# EDU_High-Speed-Design_CPU_Control.net
KiCad netlist of a schematic drawn in Altium Designer
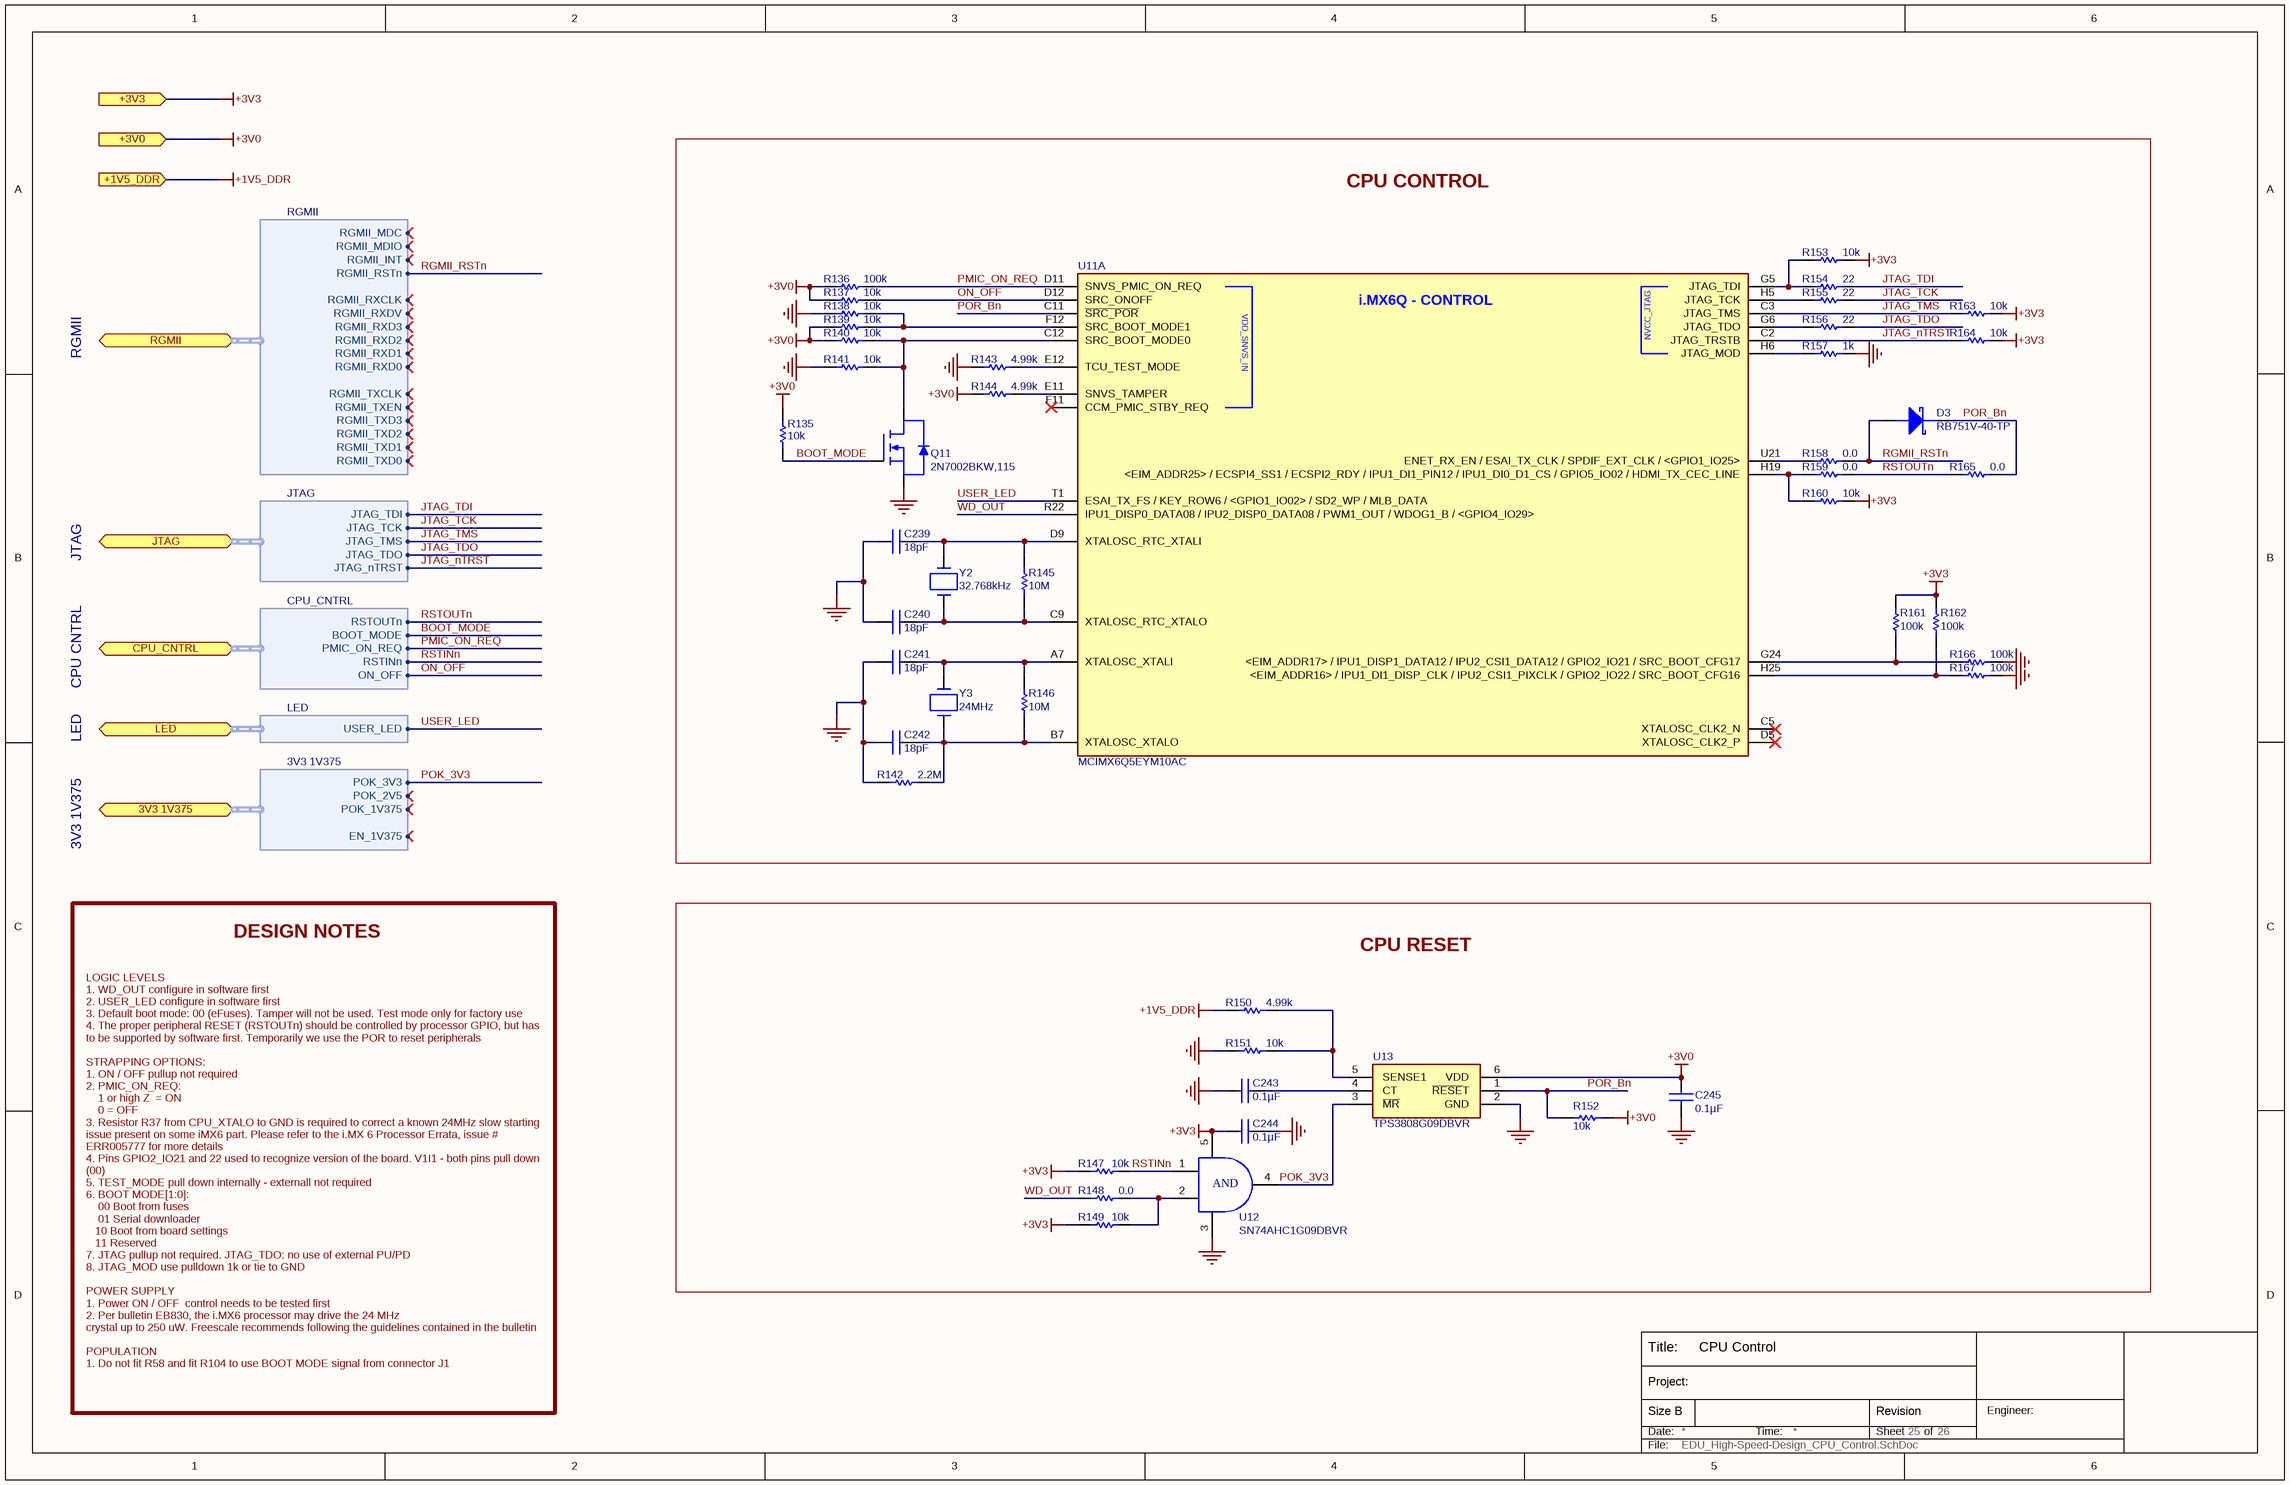
[diagram p0: EDU_High-Speed-Design_CPU_Control.SchDoc]

(export (version "E")
  (design (tool "Eeschema 10.0.6"))
  (components
    (comp (ref "C239")
      (value "18pF")
      (footprint "C0402")
      (description "CAP CER 18PF 50V C0G 5% 0402")
      (fields (field (name "VOLTAGE") "50V"))
      (libsource (lib "EDU_High-Speed-Design") (part "C1005C0G1H180J"))
    )
    (comp (ref "C240")
      (value "18pF")
      (footprint "C0402")
      (description "CAP CER 18PF 50V C0G 5% 0402")
      (fields (field (name "VOLTAGE") "50V"))
      (libsource (lib "EDU_High-Speed-Design") (part "C1005C0G1H180J"))
    )
    (comp (ref "C241")
      (value "18pF")
      (footprint "C0402")
      (description "CAP CER 18PF 50V C0G 5% 0402")
      (fields (field (name "VOLTAGE") "50V"))
      (libsource (lib "EDU_High-Speed-Design") (part "C1005C0G1H180J"))
    )
    (comp (ref "C242")
      (value "18pF")
      (footprint "C0402")
      (description "CAP CER 18PF 50V C0G 5% 0402")
      (fields (field (name "VOLTAGE") "50V"))
      (libsource (lib "EDU_High-Speed-Design") (part "C1005C0G1H180J"))
    )
    (comp (ref "C243")
      (value "0.1µF")
      (footprint "C0402")
      (description "CAP CER .10UF 50V X5R 10% 0402")
      (fields (field (name "VOLTAGE") "50V"))
      (libsource (lib "EDU_High-Speed-Design") (part "C1005X5R1H104K"))
    )
    (comp (ref "C244")
      (value "0.1µF")
      (footprint "C0402")
      (description "CAP CER .10UF 50V X5R 10% 0402")
      (fields (field (name "VOLTAGE") "50V"))
      (libsource (lib "EDU_High-Speed-Design") (part "C1005X5R1H104K"))
    )
    (comp (ref "C245")
      (value "0.1µF")
      (footprint "C0402")
      (description "CAP CER .10UF 50V X5R 10% 0402")
      (fields (field (name "VOLTAGE") "50V"))
      (libsource (lib "EDU_High-Speed-Design") (part "C1005X5R1H104K"))
    )
    (comp (ref "D3")
      (value "RB751V-40-TP")
      (footprint "SOD-323")
      (description "DIODE SCHTKY 30MA 30V SOD-323")
      (libsource (lib "EDU_High-Speed-Design") (part "RB751V-40-TP"))
    )
    (comp (ref "Q11")
      (value "2N7002BKW,115")
      (footprint "SOT-23-3")
      (description "MOSFET N-CH 60V 310MA SOT323")
      (libsource (lib "EDU_High-Speed-Design") (part "2N7002BKW,115"))
    )
    (comp (ref "R135")
      (value "10k")
      (footprint "R0402")
      (description "RES 10.0K OHM 1/16W 1% 0402 SMD")
      (libsource (lib "EDU_High-Speed-Design") (part "RC0402FR-0710KL"))
    )
    (comp (ref "R136")
      (value "100k")
      (footprint "R0402")
      (description "RES 100K OHM 1/16W 1% 0402 SMD")
      (libsource (lib "EDU_High-Speed-Design") (part "RMCF0402FT100K"))
    )
    (comp (ref "R137")
      (value "10k")
      (footprint "R0402")
      (description "RES 10.0K OHM 1/16W 1% 0402 SMD")
      (libsource (lib "EDU_High-Speed-Design") (part "RC0402FR-0710KL"))
    )
    (comp (ref "R138")
      (value "10k")
      (footprint "R0402")
      (description "RES 10.0K OHM 1/16W 1% 0402 SMD")
      (libsource (lib "EDU_High-Speed-Design") (part "RC0402FR-0710KL"))
    )
    (comp (ref "R139")
      (value "10k")
      (footprint "R0402")
      (description "RES 10.0K OHM 1/16W 1% 0402 SMD")
      (libsource (lib "EDU_High-Speed-Design") (part "RC0402FR-0710KL"))
    )
    (comp (ref "R140")
      (value "10k")
      (footprint "R0402")
      (description "RES 10.0K OHM 1/16W 1% 0402 SMD")
      (libsource (lib "EDU_High-Speed-Design") (part "RC0402FR-0710KL"))
    )
    (comp (ref "R141")
      (value "10k")
      (footprint "R0402")
      (description "RES 10.0K OHM 1/16W 1% 0402 SMD")
      (libsource (lib "EDU_High-Speed-Design") (part "RC0402FR-0710KL"))
    )
    (comp (ref "R142")
      (value "2.2M")
      (footprint "R0402")
      (description "RES 2.20M OHM 1/16W 1% 0402 SMD")
      (libsource (lib "EDU_High-Speed-Design") (part "CRCW04022M20FKED"))
    )
    (comp (ref "R143")
      (value "4.99k")
      (footprint "R0402")
      (description "RES TF 4.99K OHM 1% 1/16W 0402")
      (libsource (lib "EDU_High-Speed-Design") (part "RMCF0402FT4K99"))
    )
    (comp (ref "R144")
      (value "4.99k")
      (footprint "R0402")
      (description "RES TF 4.99K OHM 1% 1/16W 0402")
      (libsource (lib "EDU_High-Speed-Design") (part "RMCF0402FT4K99"))
    )
    (comp (ref "R145")
      (value "10M")
      (footprint "R0402")
      (description "RES 10.0M OHM 1/16W 1% 0402 SMD")
      (libsource (lib "EDU_High-Speed-Design") (part "CRCW040210M0FKED"))
    )
    (comp (ref "R146")
      (value "10M")
      (footprint "R0402")
      (description "RES 10.0M OHM 1/16W 1% 0402 SMD")
      (libsource (lib "EDU_High-Speed-Design") (part "CRCW040210M0FKED"))
    )
    (comp (ref "R147")
      (value "10k")
      (footprint "R0402")
      (description "RES 10.0K OHM 1/16W 1% 0402 SMD")
      (libsource (lib "EDU_High-Speed-Design") (part "RC0402FR-0710KL"))
    )
    (comp (ref "R148")
      (value "0.0")
      (footprint "R0402")
      (description "RES 0.0 OHM 1/16W 0402 SMD")
      (libsource (lib "EDU_High-Speed-Design") (part "RC0402JR-070RL"))
    )
    (comp (ref "R149")
      (value "10k")
      (footprint "R0402")
      (description "RES 10.0K OHM 1/16W 1% 0402 SMD")
      (libsource (lib "EDU_High-Speed-Design") (part "RC0402FR-0710KL"))
    )
    (comp (ref "R150")
      (value "4.99k")
      (footprint "R0402")
      (description "RES TF 4.99K OHM 1% 1/16W 0402")
      (libsource (lib "EDU_High-Speed-Design") (part "RMCF0402FT4K99"))
    )
    (comp (ref "R151")
      (value "10k")
      (footprint "R0402")
      (description "RES 10.0K OHM 1/16W 1% 0402 SMD")
      (libsource (lib "EDU_High-Speed-Design") (part "RC0402FR-0710KL"))
    )
    (comp (ref "R152")
      (value "10k")
      (footprint "R0402")
      (description "RES 10.0K OHM 1/16W 1% 0402 SMD")
      (libsource (lib "EDU_High-Speed-Design") (part "RC0402FR-0710KL"))
    )
    (comp (ref "R153")
      (value "10k")
      (footprint "R0402")
      (description "RES 10.0K OHM 1/16W 1% 0402 SMD")
      (libsource (lib "EDU_High-Speed-Design") (part "RC0402FR-0710KL"))
    )
    (comp (ref "R154")
      (value "22")
      (footprint "R0402")
      (description "RES 22.0 OHM 1/16W 1% 0402 SMD")
      (libsource (lib "EDU_High-Speed-Design") (part "RC0402FR-0722RL"))
    )
    (comp (ref "R155")
      (value "22")
      (footprint "R0402")
      (description "RES 22.0 OHM 1/16W 1% 0402 SMD")
      (libsource (lib "EDU_High-Speed-Design") (part "RC0402FR-0722RL"))
    )
    (comp (ref "R156")
      (value "22")
      (footprint "R0402")
      (description "RES 22.0 OHM 1/16W 1% 0402 SMD")
      (libsource (lib "EDU_High-Speed-Design") (part "RC0402FR-0722RL"))
    )
    (comp (ref "R157")
      (value "1k")
      (footprint "R0402")
      (description "RES 1.00K OHM 1/16W 1% 0402 SMD")
      (libsource (lib "EDU_High-Speed-Design") (part "RC0402FR-071KL"))
    )
    (comp (ref "R158")
      (value "0.0")
      (footprint "R0402")
      (description "RES 0.0 OHM 1/16W 0402 SMD")
      (libsource (lib "EDU_High-Speed-Design") (part "RC0402JR-070RL"))
    )
    (comp (ref "R159")
      (value "0.0")
      (footprint "R0402")
      (description "RES 0.0 OHM 1/16W 0402 SMD")
      (libsource (lib "EDU_High-Speed-Design") (part "RC0402JR-070RL"))
    )
    (comp (ref "R160")
      (value "10k")
      (footprint "R0402")
      (description "RES 10.0K OHM 1/16W 1% 0402 SMD")
      (libsource (lib "EDU_High-Speed-Design") (part "RC0402FR-0710KL"))
    )
    (comp (ref "R161")
      (value "100k")
      (footprint "R0402")
      (description "RES 100K OHM 1/16W 1% 0402 SMD")
      (libsource (lib "EDU_High-Speed-Design") (part "RMCF0402FT100K"))
    )
    (comp (ref "R162")
      (value "100k")
      (footprint "R0402")
      (description "RES 100K OHM 1/16W 1% 0402 SMD")
      (libsource (lib "EDU_High-Speed-Design") (part "RMCF0402FT100K"))
    )
    (comp (ref "R163")
      (value "10k")
      (footprint "R0402")
      (description "RES 10.0K OHM 1/16W 1% 0402 SMD")
      (libsource (lib "EDU_High-Speed-Design") (part "RC0402FR-0710KL"))
    )
    (comp (ref "R164")
      (value "10k")
      (footprint "R0402")
      (description "RES 10.0K OHM 1/16W 1% 0402 SMD")
      (libsource (lib "EDU_High-Speed-Design") (part "RC0402FR-0710KL"))
    )
    (comp (ref "R165")
      (value "0.0")
      (footprint "R0402")
      (description "RES 0.0 OHM 1/16W 0402 SMD")
      (libsource (lib "EDU_High-Speed-Design") (part "RC0402JR-070RL"))
    )
    (comp (ref "R166")
      (value "100k")
      (footprint "R0402")
      (description "RES 100K OHM 1/16W 1% 0402 SMD")
      (libsource (lib "EDU_High-Speed-Design") (part "RMCF0402FT100K"))
    )
    (comp (ref "R167")
      (value "100k")
      (footprint "R0402")
      (description "RES 100K OHM 1/16W 1% 0402 SMD")
      (libsource (lib "EDU_High-Speed-Design") (part "RMCF0402FT100K"))
    )
    (comp (ref "U11")
      (value "MCIMX6Q5EYM10AC")
      (footprint "MCIMX6Q5EYM10AC")
      (description "IC MCU 32BIT ARM QUAD 624FCBGA")
      (libsource (lib "EDU_High-Speed-Design") (part "MCIMX6Q5EYM10AC"))
    )
    (comp (ref "U12")
      (value "SN74AHC1G09DBVR")
      (footprint "SOT-23-5")
      (description "IC GATE AND SGL 2INP SOT23-5")
      (fields
        (field (name "MANUFACTURER") "Texas Instruments")
        (field (name ".CREATOR") "MM")
        (field (name ".CHECKED PCB") "RF, used by MM")
        (field (name ".CHECKED SCH") "MM, checked by RF")
      )
      (libsource (lib "EDU_High-Speed-Design") (part "SN74AHC1G09DBVR"))
    )
    (comp (ref "U13")
      (value "TPS3808G09DBVR")
      (footprint "SOT-23-6")
      (description "IC VOLT SUPERVISOR 0.9V SOT23-6")
      (libsource (lib "EDU_High-Speed-Design") (part "TPS3808G09DBVR"))
    )
    (comp (ref "Y2")
      (value "32.768kHz")
      (footprint "ABS06")
      (description "CRYSTAL 32.768 KHZ 9.0 PF SMD")
      (libsource (lib "EDU_High-Speed-Design") (part "ABS06-32.768KHZ-9-1-T"))
    )
    (comp (ref "Y3")
      (value "24MHz")
      (footprint "ABM7")
      (description "CRYSTAL 24.0000MHZ 18PF SMD")
      (libsource (lib "EDU_High-Speed-Design") (part "ABM7-24.000MHZ-D-2-Y-T"))
    )
  )
  (nets
    (net (code "7") (name "+1V5_DDR") (class "Default")
      (node (ref "R150") (pin "2") (pinfunction "2_2") (pintype "passive"))
    )
    (net (code "8") (name "+3V0") (class "Default")
      (node (ref "C245") (pin "1") (pinfunction "1_1") (pintype "passive"))
      (node (ref "R135") (pin "2") (pinfunction "2_2") (pintype "passive"))
      (node (ref "R136") (pin "2") (pinfunction "2_2") (pintype "passive"))
      (node (ref "R137") (pin "1") (pinfunction "1_1") (pintype "passive"))
      (node (ref "R139") (pin "1") (pinfunction "1_1") (pintype "passive"))
      (node (ref "R140") (pin "1") (pinfunction "1_1") (pintype "passive"))
      (node (ref "R144") (pin "2") (pinfunction "2_2") (pintype "passive"))
      (node (ref "R152") (pin "1") (pinfunction "1_1") (pintype "passive"))
      (node (ref "U13") (pin "6") (pinfunction "VDD_6") (pintype "passive"))
    )
    (net (code "9") (name "+3V3") (class "Default")
      (node (ref "C244") (pin "1") (pinfunction "1_1") (pintype "passive"))
      (node (ref "R147") (pin "2") (pinfunction "2_2") (pintype "passive"))
      (node (ref "R149") (pin "2") (pinfunction "2_2") (pintype "passive"))
      (node (ref "R153") (pin "2") (pinfunction "2_2") (pintype "passive"))
      (node (ref "R160") (pin "2") (pinfunction "2_2") (pintype "passive"))
      (node (ref "R161") (pin "1") (pinfunction "1_1") (pintype "passive"))
      (node (ref "R162") (pin "1") (pinfunction "1_1") (pintype "passive"))
      (node (ref "R163") (pin "2") (pinfunction "2_2") (pintype "passive"))
      (node (ref "R164") (pin "2") (pinfunction "2_2") (pintype "passive"))
      (node (ref "U12") (pin "5") (pinfunction "VCC_5") (pintype "passive"))
    )
    (net (code "10") (name "/BOOT_MODE") (class "Default")
      (node (ref "Q11") (pin "1") (pinfunction "G_1") (pintype "passive"))
      (node (ref "R135") (pin "1") (pinfunction "1_1") (pintype "passive"))
    )
    (net (code "11") (name "/JTAG_TCK") (class "Default")
      (node (ref "R155") (pin "1") (pinfunction "1_1") (pintype "passive"))
    )
    (net (code "12") (name "/JTAG_TDI") (class "Default")
      (node (ref "R154") (pin "1") (pinfunction "1_1") (pintype "passive"))
    )
    (net (code "13") (name "/JTAG_TDO") (class "Default")
      (node (ref "R156") (pin "1") (pinfunction "1_1") (pintype "passive"))
    )
    (net (code "14") (name "/JTAG_TMS") (class "Default")
      (node (ref "R163") (pin "1") (pinfunction "1_1") (pintype "passive"))
      (node (ref "U11") (pin "C3") (pinfunction "JTAG_TMS_C3") (pintype "passive"))
    )
    (net (code "15") (name "/JTAG_nTRST") (class "Default")
      (node (ref "R164") (pin "1") (pinfunction "1_1") (pintype "passive"))
      (node (ref "U11") (pin "C2") (pinfunction "JTAG_TRSTB_C2") (pintype "passive"))
    )
    (net (code "16") (name "/ON_OFF") (class "Default")
      (node (ref "R137") (pin "2") (pinfunction "2_2") (pintype "passive"))
      (node (ref "U11") (pin "D12") (pinfunction "SRC_ONOFF_D12") (pintype "passive"))
    )
    (net (code "17") (name "/PMIC_ON_REQ") (class "Default")
      (node (ref "R136") (pin "1") (pinfunction "1_1") (pintype "passive"))
      (node (ref "U11") (pin "D11") (pinfunction "SNVS_PMIC_ON_REQ_D11") (pintype "passive"))
    )
    (net (code "18") (name "/POK_3V3") (class "Default")
      (node (ref "U12") (pin "4") (pinfunction "Y_4") (pintype "passive"))
      (node (ref "U13") (pin "3") (pinfunction "~{MR}_3") (pintype "passive"))
    )
    (net (code "19") (name "/POR_Bn") (class "Default")
      (node (ref "D3") (pin "1") (pinfunction "cathode_1") (pintype "passive"))
      (node (ref "R152") (pin "2") (pinfunction "2_2") (pintype "passive"))
      (node (ref "R165") (pin "2") (pinfunction "2_2") (pintype "passive"))
      (node (ref "U11") (pin "C11") (pinfunction "~{SRC_POR}_C11") (pintype "passive"))
      (node (ref "U13") (pin "1") (pinfunction "~{RESE}T_1") (pintype "passive"))
    )
    (net (code "20") (name "/RGMII_RSTn") (class "Default")
      (node (ref "D3") (pin "2") (pinfunction "ANODE_2") (pintype "passive"))
      (node (ref "R158") (pin "2") (pinfunction "2_2") (pintype "passive"))
    )
    (net (code "21") (name "/RSTINn") (class "Default")
      (node (ref "R147") (pin "1") (pinfunction "1_1") (pintype "passive"))
      (node (ref "U12") (pin "1") (pinfunction "A_1") (pintype "passive"))
    )
    (net (code "22") (name "/RSTOUTn") (class "Default")
      (node (ref "R159") (pin "2") (pinfunction "2_2") (pintype "passive"))
      (node (ref "R165") (pin "1") (pinfunction "1_1") (pintype "passive"))
    )
    (net (code "23") (name "/USER_LED") (class "Default")
      (node (ref "U11") (pin "T1") (pinfunction "ESAI_TX_FS_/_KEY_ROW6_/_<GPIO1_IO02>_/_SD2_WP_/_MLB_DATA_T1") (pintype "passive"))
    )
    (net (code "24") (name "/WD_OUT") (class "Default")
      (node (ref "R148") (pin "1") (pinfunction "1_1") (pintype "passive"))
      (node (ref "U11") (pin "R22") (pinfunction "IPU1_DISP0_DATA08_/_IPU2_DISP0_DATA08_/_PWM1_OUT_/_WDOG1_B_/_<GPIO4_IO29>_R22") (pintype "passive"))
    )
    (net (code "30") (name "GND") (class "Default")
      (node (ref "C239") (pin "1") (pinfunction "1_1") (pintype "passive"))
      (node (ref "C240") (pin "1") (pinfunction "1_1") (pintype "passive"))
      (node (ref "C241") (pin "1") (pinfunction "1_1") (pintype "passive"))
      (node (ref "C242") (pin "1") (pinfunction "1_1") (pintype "passive"))
      (node (ref "C243") (pin "1") (pinfunction "1_1") (pintype "passive"))
      (node (ref "C244") (pin "2") (pinfunction "2_2") (pintype "passive"))
      (node (ref "C245") (pin "2") (pinfunction "2_2") (pintype "passive"))
      (node (ref "Q11") (pin "2") (pinfunction "S_2") (pintype "passive"))
      (node (ref "R138") (pin "1") (pinfunction "1_1") (pintype "passive"))
      (node (ref "R141") (pin "1") (pinfunction "1_1") (pintype "passive"))
      (node (ref "R142") (pin "2") (pinfunction "2_2") (pintype "passive"))
      (node (ref "R143") (pin "2") (pinfunction "2_2") (pintype "passive"))
      (node (ref "R151") (pin "2") (pinfunction "2_2") (pintype "passive"))
      (node (ref "R157") (pin "1") (pinfunction "1_1") (pintype "passive"))
      (node (ref "R166") (pin "2") (pinfunction "2_2") (pintype "passive"))
      (node (ref "R167") (pin "2") (pinfunction "2_2") (pintype "passive"))
      (node (ref "U12") (pin "3") (pinfunction "GND_3") (pintype "passive"))
      (node (ref "U13") (pin "2") (pinfunction "GND_2") (pintype "passive"))
    )
    (net (code "31") (name "Net-(Q11-D)") (class "Default")
      (node (ref "Q11") (pin "3") (pinfunction "D_3") (pintype "passive"))
      (node (ref "R140") (pin "2") (pinfunction "2_2") (pintype "passive"))
      (node (ref "R141") (pin "2") (pinfunction "2_2") (pintype "passive"))
      (node (ref "U11") (pin "C12") (pinfunction "SRC_BOOT_MODE0_C12") (pintype "passive"))
    )
    (net (code "32") (name "Net-(U11A-<EIM_ADDR16>_{slash}_IPU1_DI1_DISP_CLK_{slash}_IPU2_CSI1_PIXCLK_{slash}_GPIO2_IO22_{slash}_SRC_BOOT_CFG16)") (class "Default")
      (node (ref "R162") (pin "2") (pinfunction "2_2") (pintype "passive"))
      (node (ref "R167") (pin "1") (pinfunction "1_1") (pintype "passive"))
      (node (ref "U11") (pin "H25") (pinfunction "<EIM_ADDR16>_/_IPU1_DI1_DISP_CLK_/_IPU2_CSI1_PIXCLK_/_GPIO2_IO22_/_SRC_BOOT_CFG16_H25") (pintype "passive"))
    )
    (net (code "33") (name "Net-(U11A-<EIM_ADDR17>_{slash}_IPU1_DISP1_DATA12_{slash}_IPU2_CSI1_DATA12_{slash}_GPIO2_IO21_{slash}_SRC_BOOT_CFG17)") (class "Default")
      (node (ref "R161") (pin "2") (pinfunction "2_2") (pintype "passive"))
      (node (ref "R166") (pin "1") (pinfunction "1_1") (pintype "passive"))
      (node (ref "U11") (pin "G24") (pinfunction "<EIM_ADDR17>_/_IPU1_DISP1_DATA12_/_IPU2_CSI1_DATA12_/_GPIO2_IO21_/_SRC_BOOT_CFG17_G24") (pintype "passive"))
    )
    (net (code "34") (name "Net-(U11A-<EIM_ADDR25>_{slash}_ECSPI4_SS1_{slash}_ECSPI2_RDY_{slash}_IPU1_DI1_PIN12_{slash}_IPU1_DI0_D1_CS_{slash}_GPIO5_IO02_{slash}_HDMI_TX_CEC_LINE)") (class "Default")
      (node (ref "R159") (pin "1") (pinfunction "1_1") (pintype "passive"))
      (node (ref "R160") (pin "1") (pinfunction "1_1") (pintype "passive"))
      (node (ref "U11") (pin "H19") (pinfunction "<EIM_ADDR25>_/_ECSPI4_SS1_/_ECSPI2_RDY_/_IPU1_DI1_PIN12_/_IPU1_DI0_D1_CS_/_GPIO5_IO02_/_HDMI_TX_CEC_LINE_H19") (pintype "passive"))
    )
    (net (code "35") (name "Net-(U11A-ENET_RX_EN_{slash}_ESAI_TX_CLK_{slash}_SPDIF_EXT_CLK_{slash}_<GPIO1_IO25>)") (class "Default")
      (node (ref "R158") (pin "1") (pinfunction "1_1") (pintype "passive"))
      (node (ref "U11") (pin "U21") (pinfunction "ENET_RX_EN_/_ESAI_TX_CLK_/_SPDIF_EXT_CLK_/_<GPIO1_IO25>_U21") (pintype "passive"))
    )
    (net (code "36") (name "Net-(U11A-JTAG_MOD)") (class "Default")
      (node (ref "R157") (pin "2") (pinfunction "2_2") (pintype "passive"))
      (node (ref "U11") (pin "H6") (pinfunction "JTAG_MOD_H6") (pintype "passive"))
    )
    (net (code "37") (name "Net-(U11A-JTAG_TCK)") (class "Default")
      (node (ref "R155") (pin "2") (pinfunction "2_2") (pintype "passive"))
      (node (ref "U11") (pin "H5") (pinfunction "JTAG_TCK_H5") (pintype "passive"))
    )
    (net (code "38") (name "Net-(U11A-JTAG_TDI)") (class "Default")
      (node (ref "R153") (pin "1") (pinfunction "1_1") (pintype "passive"))
      (node (ref "R154") (pin "2") (pinfunction "2_2") (pintype "passive"))
      (node (ref "U11") (pin "G5") (pinfunction "JTAG_TDI_G5") (pintype "passive"))
    )
    (net (code "39") (name "Net-(U11A-JTAG_TDO)") (class "Default")
      (node (ref "R156") (pin "2") (pinfunction "2_2") (pintype "passive"))
      (node (ref "U11") (pin "G6") (pinfunction "JTAG_TDO_G6") (pintype "passive"))
    )
    (net (code "40") (name "Net-(U11A-SNVS_TAMPER)") (class "Default")
      (node (ref "R144") (pin "1") (pinfunction "1_1") (pintype "passive"))
      (node (ref "U11") (pin "E11") (pinfunction "SNVS_TAMPER_E11") (pintype "passive"))
    )
    (net (code "41") (name "Net-(U11A-SRC_BOOT_MODE1)") (class "Default")
      (node (ref "R138") (pin "2") (pinfunction "2_2") (pintype "passive"))
      (node (ref "R139") (pin "2") (pinfunction "2_2") (pintype "passive"))
      (node (ref "U11") (pin "F12") (pinfunction "SRC_BOOT_MODE1_F12") (pintype "passive"))
    )
    (net (code "42") (name "Net-(U11A-TCU_TEST_MODE)") (class "Default")
      (node (ref "R143") (pin "1") (pinfunction "1_1") (pintype "passive"))
      (node (ref "U11") (pin "E12") (pinfunction "TCU_TEST_MODE_E12") (pintype "passive"))
    )
    (net (code "43") (name "Net-(U11A-XTALOSC_RTC_XTALI)") (class "Default")
      (node (ref "C239") (pin "2") (pinfunction "2_2") (pintype "passive"))
      (node (ref "R145") (pin "1") (pinfunction "1_1") (pintype "passive"))
      (node (ref "U11") (pin "D9") (pinfunction "XTALOSC_RTC_XTALI_D9") (pintype "passive"))
      (node (ref "Y2") (pin "2") (pinfunction "2_2") (pintype "passive"))
    )
    (net (code "44") (name "Net-(U11A-XTALOSC_RTC_XTALO)") (class "Default")
      (node (ref "C240") (pin "2") (pinfunction "2_2") (pintype "passive"))
      (node (ref "R145") (pin "2") (pinfunction "2_2") (pintype "passive"))
      (node (ref "U11") (pin "C9") (pinfunction "XTALOSC_RTC_XTALO_C9") (pintype "passive"))
      (node (ref "Y2") (pin "1") (pinfunction "1_1") (pintype "passive"))
    )
    (net (code "45") (name "Net-(U11A-XTALOSC_XTALI)") (class "Default")
      (node (ref "C241") (pin "2") (pinfunction "2_2") (pintype "passive"))
      (node (ref "R146") (pin "1") (pinfunction "1_1") (pintype "passive"))
      (node (ref "U11") (pin "A7") (pinfunction "XTALOSC_XTALI_A7") (pintype "passive"))
      (node (ref "Y3") (pin "2") (pinfunction "2_2") (pintype "passive"))
    )
    (net (code "46") (name "Net-(U11A-XTALOSC_XTALO)") (class "Default")
      (node (ref "C242") (pin "2") (pinfunction "2_2") (pintype "passive"))
      (node (ref "R142") (pin "1") (pinfunction "1_1") (pintype "passive"))
      (node (ref "R146") (pin "2") (pinfunction "2_2") (pintype "passive"))
      (node (ref "U11") (pin "B7") (pinfunction "XTALOSC_XTALO_B7") (pintype "passive"))
      (node (ref "Y3") (pin "1") (pinfunction "1_1") (pintype "passive"))
    )
    (net (code "47") (name "Net-(U12-B)") (class "Default")
      (node (ref "R148") (pin "2") (pinfunction "2_2") (pintype "passive"))
      (node (ref "R149") (pin "1") (pinfunction "1_1") (pintype "passive"))
      (node (ref "U12") (pin "2") (pinfunction "B_2") (pintype "passive"))
    )
    (net (code "48") (name "Net-(U13-CT)") (class "Default")
      (node (ref "C243") (pin "2") (pinfunction "2_2") (pintype "passive"))
      (node (ref "U13") (pin "4") (pinfunction "CT_4") (pintype "passive"))
    )
    (net (code "49") (name "Net-(U13-SENSE1)") (class "Default")
      (node (ref "R150") (pin "1") (pinfunction "1_1") (pintype "passive"))
      (node (ref "R151") (pin "1") (pinfunction "1_1") (pintype "passive"))
      (node (ref "U13") (pin "5") (pinfunction "SENSE1_5") (pintype "passive"))
    )
    (net (code "50") (name "unconnected-(U11A-CCM_PMIC_STBY_REQ-PadF11)") (class "Default")
      (node (ref "U11") (pin "F11") (pinfunction "CCM_PMIC_STBY_REQ_F11") (pintype "passive+no_connect"))
    )
    (net (code "51") (name "unconnected-(U11A-XTALOSC_CLK2_N-PadC5)") (class "Default")
      (node (ref "U11") (pin "C5") (pinfunction "XTALOSC_CLK2_N_C5") (pintype "passive+no_connect"))
    )
    (net (code "52") (name "unconnected-(U11A-XTALOSC_CLK2_P-PadD5)") (class "Default")
      (node (ref "U11") (pin "D5") (pinfunction "XTALOSC_CLK2_P_D5") (pintype "passive+no_connect"))
    )
  )
)
